# Fubarino_SD_v15.net
KiCad netlist of a schematic drawn in EAGLE
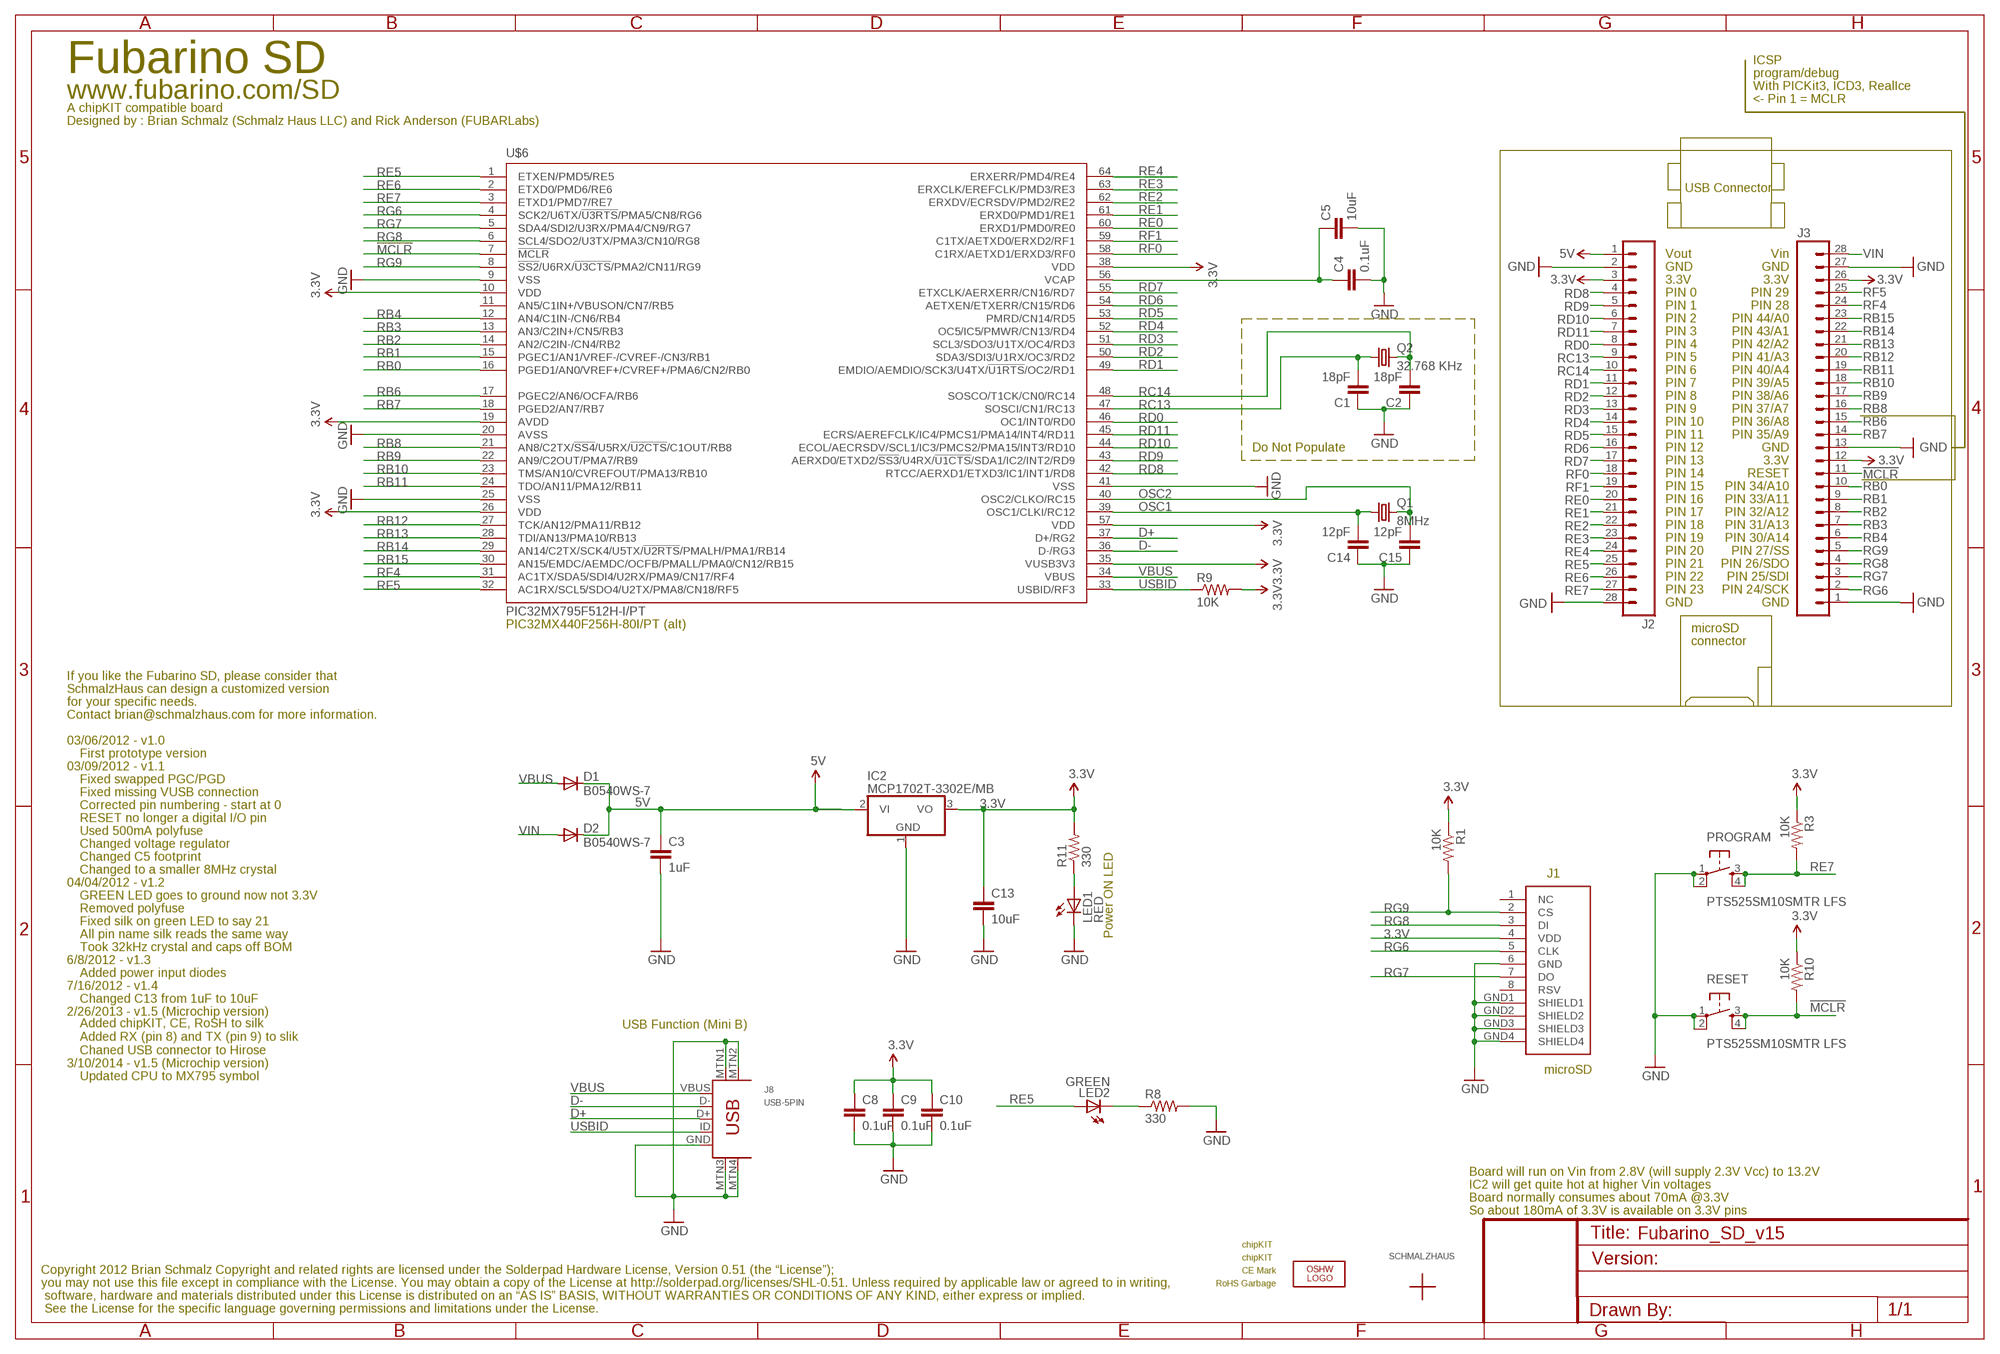
[diagram p0: schematic, sheet 1]

(export (version "E")
  (design (tool "Eeschema 10.0.6"))
  (components
    (comp (ref "C1")
      (value "18pF")
      (footprint "eagle-import:0603-CAP")
      (libsource (lib "eagle-import") (part "SparkFun_CAP0603-CAP"))
    )
    (comp (ref "C2")
      (value "18pF")
      (footprint "eagle-import:0603-CAP")
      (libsource (lib "eagle-import") (part "SparkFun_CAP0603-CAP"))
    )
    (comp (ref "C3")
      (value "1uF")
      (footprint "eagle-import:0603-CAP")
      (libsource (lib "eagle-import") (part "SparkFun_CAP0603-CAP"))
    )
    (comp (ref "C4")
      (value "0.1uF")
      (footprint "eagle-import:0603-CAP")
      (libsource (lib "eagle-import") (part "SparkFun_CAP0603-CAP"))
    )
    (comp (ref "C5")
      (value "10uF")
      (footprint "eagle-import:0805")
      (libsource (lib "eagle-import") (part "CAP0805"))
    )
    (comp (ref "C8")
      (value "0.1uF")
      (footprint "eagle-import:0603-CAP")
      (libsource (lib "eagle-import") (part "SparkFun_CAP0603-CAP"))
    )
    (comp (ref "C9")
      (value "0.1uF")
      (footprint "eagle-import:0603-CAP")
      (libsource (lib "eagle-import") (part "SparkFun_CAP0603-CAP"))
    )
    (comp (ref "C10")
      (value "0.1uF")
      (footprint "eagle-import:0603")
      (libsource (lib "eagle-import") (part "CAP0603"))
    )
    (comp (ref "C13")
      (value "10uF")
      (footprint "eagle-import:0805")
      (libsource (lib "eagle-import") (part "SparkFun02-20-08_CAP0805"))
    )
    (comp (ref "C14")
      (value "12pF")
      (footprint "eagle-import:0603-CAP")
      (libsource (lib "eagle-import") (part "SparkFun_CAP0603-CAP"))
    )
    (comp (ref "C15")
      (value "12pF")
      (footprint "eagle-import:0603-CAP")
      (libsource (lib "eagle-import") (part "SparkFun_CAP0603-CAP"))
    )
    (comp (ref "D1")
      (value "B0540WS-7")
      (footprint "eagle-import:SOD-323")
      (libsource (lib "eagle-import") (part "DIODESOD"))
    )
    (comp (ref "D2")
      (value "B0540WS-7")
      (footprint "eagle-import:SOD-323")
      (libsource (lib "eagle-import") (part "DIODESOD"))
    )
    (comp (ref "IC2")
      (value "MCP1702T-3302E/MB")
      (footprint "eagle-import:SOT89")
      (libsource (lib "eagle-import") (part "MCP1703MB33"))
    )
    (comp (ref "J1")
      (value "MICRO_SD_CARD_SOCKET")
      (footprint "eagle-import:SD-MMC_SOCKET-PP")
      (libsource (lib "eagle-import") (part "MICRO_SD_CARD_SOCKET"))
    )
    (comp (ref "J2")
      (value "M28USEPIN1")
      (footprint "eagle-import:1X28")
      (libsource (lib "eagle-import") (part "M28USEPIN1"))
    )
    (comp (ref "J3")
      (value "M28NOPIN1")
      (footprint "eagle-import:1X28_NO_PIN_1")
      (libsource (lib "eagle-import") (part "M28NOPIN1"))
    )
    (comp (ref "J8")
      (value "USB-5PIN")
      (footprint "eagle-import:USB-MINIB-5PIN-HIROSE-UX60-MB-5ST")
      (libsource (lib "eagle-import") (part "USB-5PIN"))
    )
    (comp (ref "LED1")
      (value "RED")
      (footprint "eagle-import:LED-0603")
      (libsource (lib "eagle-import") (part "LED0603"))
    )
    (comp (ref "LED2")
      (value "GREEN")
      (footprint "eagle-import:LED-0603")
      (libsource (lib "eagle-import") (part "LED0603"))
    )
    (comp (ref "LOGO1")
      (value "OSHW_LOGO_8MILX0070-NT")
      (footprint "eagle-import:OSHW_8X70_NOTEXT")
      (libsource (lib "eagle-import") (part "OSHW_LOGO_8MILX0070-NT"))
    )
    (comp (ref "PROGRAM")
      (value "PTS525SM10SMTR LFS")
      (footprint "eagle-import:TACTILE_SWITCH_SMD")
      (libsource (lib "eagle-import") (part "TAC_SWITCHSND"))
    )
    (comp (ref "Q1")
      (value "8MHz")
      (footprint "eagle-import:NX5032_5MM_3.2MM_CRYSTAL")
      (libsource (lib "eagle-import") (part "CRYSTALNX5032"))
    )
    (comp (ref "Q2")
      (value "32.768 KHz")
      (footprint "eagle-import:TC26H")
      (libsource (lib "eagle-import") (part "CRYSTALTC26H"))
    )
    (comp (ref "R1")
      (value "10K")
      (footprint "eagle-import:0603-RES")
      (libsource (lib "eagle-import") (part "RESISTOR0603-RES"))
    )
    (comp (ref "R3")
      (value "10K")
      (footprint "eagle-import:0603-RES")
      (libsource (lib "eagle-import") (part "RESISTOR0603-RES"))
    )
    (comp (ref "R8")
      (value "330")
      (footprint "eagle-import:0603-RES")
      (libsource (lib "eagle-import") (part "RESISTOR0603-RES"))
    )
    (comp (ref "R9")
      (value "10K")
      (footprint "eagle-import:0603-RES")
      (libsource (lib "eagle-import") (part "RESISTOR0603-RES"))
    )
    (comp (ref "R10")
      (value "10K")
      (footprint "eagle-import:0603-RES")
      (libsource (lib "eagle-import") (part "RESISTOR0603-RES"))
    )
    (comp (ref "R11")
      (value "330")
      (footprint "eagle-import:0603-RES")
      (libsource (lib "eagle-import") (part "RESISTOR0603-RES"))
    )
    (comp (ref "RESET")
      (value "PTS525SM10SMTR LFS")
      (footprint "eagle-import:TACTILE_SWITCH_SMD")
      (libsource (lib "eagle-import") (part "TAC_SWITCHSND"))
    )
    (comp (ref "U$1")
      (value "SCHMALZHAUSSCHMALZHAUS_SMALL")
      (footprint "eagle-import:SCHMALZHAUS_SMALL")
      (libsource (lib "eagle-import") (part "SCHMALZHAUSSCHMALZHAUS_SMALL"))
    )
    (comp (ref "U$2")
      (value "CE_MARK5MM")
      (footprint "eagle-import:CE_5MM")
      (libsource (lib "eagle-import") (part "CE_MARK5MM"))
    )
    (comp (ref "U$3")
      (value "ROHS_GARBAGE")
      (footprint "eagle-import:ROHS_GARBAGE_5MM")
      (libsource (lib "eagle-import") (part "ROHS_GARBAGE"))
    )
    (comp (ref "U$4")
      (value "CHIPKIT2MM")
      (footprint "eagle-import:CHIPKIT_2MM")
      (libsource (lib "eagle-import") (part "CHIPKIT2MM"))
    )
    (comp (ref "U$5")
      (value "CHIPKIT2MM")
      (footprint "eagle-import:CHIPKIT_2MM")
      (libsource (lib "eagle-import") (part "CHIPKIT2MM"))
    )
    (comp (ref "U$6")
      (value "PIC32MX795F512H-I/PT")
      (footprint "eagle-import:TQFP64-10X10")
      (libsource (lib "eagle-import") (part "PIC32MX795F512H-I/PT"))
    )
  )
  (nets
    (net (code "1") (name "/D+") (class "Default")
      (node (ref "J8") (pin "D+") (pinfunction "D+_D+") (pintype "bidirectional"))
      (node (ref "U$6") (pin "37") (pinfunction "D+/RG2_37") (pintype "bidirectional"))
    )
    (net (code "2") (name "/D-") (class "Default")
      (node (ref "J8") (pin "D-") (pinfunction "D-_D-") (pintype "bidirectional"))
      (node (ref "U$6") (pin "36") (pinfunction "D-/RG3_36") (pintype "bidirectional"))
    )
    (net (code "3") (name "/OSC1") (class "Default")
      (node (ref "C14") (pin "2") (pinfunction "2_2") (pintype "passive"))
      (node (ref "Q1") (pin "1") (pinfunction "1_1") (pintype "passive"))
      (node (ref "U$6") (pin "39") (pinfunction "OSC1/CLKI/RC12_39") (pintype "bidirectional"))
    )
    (net (code "4") (name "/OSC2") (class "Default")
      (node (ref "C15") (pin "2") (pinfunction "2_2") (pintype "passive"))
      (node (ref "Q1") (pin "2") (pinfunction "2_2") (pintype "passive"))
      (node (ref "U$6") (pin "40") (pinfunction "OSC2/CLKO/RC15_40") (pintype "bidirectional"))
    )
    (net (code "5") (name "/RB0") (class "Default")
      (node (ref "J3") (pin "10") (pinfunction "10_10") (pintype "passive"))
      (node (ref "U$6") (pin "16") (pinfunction "PGED1/AN0/VREF+/CVREF+/PMA6/CN2/RB0_16") (pintype "bidirectional"))
    )
    (net (code "6") (name "/RB1") (class "Default")
      (node (ref "J3") (pin "9") (pinfunction "9_9") (pintype "passive"))
      (node (ref "U$6") (pin "15") (pinfunction "PGEC1/AN1/VREF-/CVREF-/CN3/RB1_15") (pintype "bidirectional"))
    )
    (net (code "7") (name "/RB2") (class "Default")
      (node (ref "J3") (pin "8") (pinfunction "8_8") (pintype "passive"))
      (node (ref "U$6") (pin "14") (pinfunction "AN2/C2IN-/CN4/RB2_14") (pintype "bidirectional"))
    )
    (net (code "8") (name "/RB3") (class "Default")
      (node (ref "J3") (pin "7") (pinfunction "7_7") (pintype "passive"))
      (node (ref "U$6") (pin "13") (pinfunction "AN3/C2IN+/CN5/RB3_13") (pintype "bidirectional"))
    )
    (net (code "9") (name "/RB4") (class "Default")
      (node (ref "J3") (pin "6") (pinfunction "6_6") (pintype "passive"))
      (node (ref "U$6") (pin "12") (pinfunction "AN4/C1IN-/CN6/RB4_12") (pintype "bidirectional"))
    )
    (net (code "10") (name "/RB6") (class "Default")
      (node (ref "J3") (pin "15") (pinfunction "15_15") (pintype "passive"))
      (node (ref "U$6") (pin "17") (pinfunction "PGEC2/AN6/OCFA/RB6_17") (pintype "bidirectional"))
    )
    (net (code "11") (name "/RB7") (class "Default")
      (node (ref "J3") (pin "14") (pinfunction "14_14") (pintype "passive"))
      (node (ref "U$6") (pin "18") (pinfunction "PGED2/AN7/RB7_18") (pintype "bidirectional"))
    )
    (net (code "12") (name "/RB8") (class "Default")
      (node (ref "J3") (pin "16") (pinfunction "16_16") (pintype "passive"))
      (node (ref "U$6") (pin "21") (pinfunction "AN8/C2TX/~{SS4}/U5RX/~{U2CTS}/C1OUT/RB8_21") (pintype "bidirectional"))
    )
    (net (code "13") (name "/RB9") (class "Default")
      (node (ref "J3") (pin "17") (pinfunction "17_17") (pintype "passive"))
      (node (ref "U$6") (pin "22") (pinfunction "AN9/C2OUT/PMA7/RB9_22") (pintype "bidirectional"))
    )
    (net (code "14") (name "/RB10") (class "Default")
      (node (ref "J3") (pin "18") (pinfunction "18_18") (pintype "passive"))
      (node (ref "U$6") (pin "23") (pinfunction "TMS/AN10/CVREFOUT/PMA13/RB10_23") (pintype "input"))
    )
    (net (code "15") (name "/RB11") (class "Default")
      (node (ref "J3") (pin "19") (pinfunction "19_19") (pintype "passive"))
      (node (ref "U$6") (pin "24") (pinfunction "TDO/AN11/PMA12/RB11_24") (pintype "bidirectional"))
    )
    (net (code "16") (name "/RB12") (class "Default")
      (node (ref "J3") (pin "20") (pinfunction "20_20") (pintype "passive"))
      (node (ref "U$6") (pin "27") (pinfunction "TCK/AN12/PMA11/RB12_27") (pintype "input"))
    )
    (net (code "17") (name "/RB13") (class "Default")
      (node (ref "J3") (pin "21") (pinfunction "21_21") (pintype "passive"))
      (node (ref "U$6") (pin "28") (pinfunction "TDI/AN13/PMA10/RB13_28") (pintype "input"))
    )
    (net (code "18") (name "/RB14") (class "Default")
      (node (ref "J3") (pin "22") (pinfunction "22_22") (pintype "passive"))
      (node (ref "U$6") (pin "29") (pinfunction "AN14/C2TX/SCK4/U5TX/~{U2RTS}/PMALH/PMA1/RB14_29") (pintype "bidirectional"))
    )
    (net (code "19") (name "/RB15") (class "Default")
      (node (ref "J3") (pin "23") (pinfunction "23_23") (pintype "passive"))
      (node (ref "U$6") (pin "30") (pinfunction "AN15/EMDC/AEMDC/OCFB/PMALL/PMA0/CN12/RB15_30") (pintype "bidirectional"))
    )
    (net (code "20") (name "/RC13") (class "Default")
      (node (ref "C1") (pin "2") (pinfunction "2_2") (pintype "passive"))
      (node (ref "J2") (pin "9") (pinfunction "9_9") (pintype "passive"))
      (node (ref "Q2") (pin "1") (pinfunction "1_1") (pintype "passive"))
      (node (ref "U$6") (pin "47") (pinfunction "SOSCI/CN1/RC13_47") (pintype "bidirectional"))
    )
    (net (code "21") (name "/RC14") (class "Default")
      (node (ref "C2") (pin "2") (pinfunction "2_2") (pintype "passive"))
      (node (ref "J2") (pin "10") (pinfunction "10_10") (pintype "passive"))
      (node (ref "Q2") (pin "2") (pinfunction "2_2") (pintype "passive"))
      (node (ref "U$6") (pin "48") (pinfunction "SOSCO/T1CK/CN0/RC14_48") (pintype "bidirectional"))
    )
    (net (code "22") (name "/RD0") (class "Default")
      (node (ref "J2") (pin "8") (pinfunction "8_8") (pintype "passive"))
      (node (ref "U$6") (pin "46") (pinfunction "OC1/INT0/RD0_46") (pintype "bidirectional"))
    )
    (net (code "23") (name "/RD1") (class "Default")
      (node (ref "J2") (pin "11") (pinfunction "11_11") (pintype "passive"))
      (node (ref "U$6") (pin "49") (pinfunction "EMDIO/AEMDIO/SCK3/U4TX/~{U1RTS}/OC2/RD1_49") (pintype "bidirectional"))
    )
    (net (code "24") (name "/RD2") (class "Default")
      (node (ref "J2") (pin "12") (pinfunction "12_12") (pintype "passive"))
      (node (ref "U$6") (pin "50") (pinfunction "SDA3/SDI3/U1RX/OC3/RD2_50") (pintype "bidirectional"))
    )
    (net (code "25") (name "/RD3") (class "Default")
      (node (ref "J2") (pin "13") (pinfunction "13_13") (pintype "passive"))
      (node (ref "U$6") (pin "51") (pinfunction "SCL3/SDO3/U1TX/OC4/RD3_51") (pintype "bidirectional"))
    )
    (net (code "26") (name "/RD4") (class "Default")
      (node (ref "J2") (pin "14") (pinfunction "14_14") (pintype "passive"))
      (node (ref "U$6") (pin "52") (pinfunction "OC5/IC5/PMWR/CN13/RD4_52") (pintype "bidirectional"))
    )
    (net (code "27") (name "/RD5") (class "Default")
      (node (ref "J2") (pin "15") (pinfunction "15_15") (pintype "passive"))
      (node (ref "U$6") (pin "53") (pinfunction "PMRD/CN14/RD5_53") (pintype "bidirectional"))
    )
    (net (code "28") (name "/RD6") (class "Default")
      (node (ref "J2") (pin "16") (pinfunction "16_16") (pintype "passive"))
      (node (ref "U$6") (pin "54") (pinfunction "AETXEN/ETXERR/CN15/RD6_54") (pintype "bidirectional"))
    )
    (net (code "29") (name "/RD7") (class "Default")
      (node (ref "J2") (pin "17") (pinfunction "17_17") (pintype "passive"))
      (node (ref "U$6") (pin "55") (pinfunction "ETXCLK/AERXERR/CN16/RD7_55") (pintype "bidirectional"))
    )
    (net (code "30") (name "/RD8") (class "Default")
      (node (ref "J2") (pin "4") (pinfunction "4_4") (pintype "passive"))
      (node (ref "U$6") (pin "42") (pinfunction "RTCC/AERXD1/ETXD3/IC1/INT1/RD8_42") (pintype "bidirectional"))
    )
    (net (code "31") (name "/RD9") (class "Default")
      (node (ref "J2") (pin "5") (pinfunction "5_5") (pintype "passive"))
      (node (ref "U$6") (pin "43") (pinfunction "AERXD0/ETXD2/~{SS3}/U4RX/~{U1CTS}/SDA1/IC2/INT2/RD9_43") (pintype "bidirectional"))
    )
    (net (code "32") (name "/RD10") (class "Default")
      (node (ref "J2") (pin "6") (pinfunction "6_6") (pintype "passive"))
      (node (ref "U$6") (pin "44") (pinfunction "ECOL/AECRSDV/SCL1/IC3/PMCS2/PMA15/INT3/RD10_44") (pintype "bidirectional"))
    )
    (net (code "33") (name "/RD11") (class "Default")
      (node (ref "J2") (pin "7") (pinfunction "7_7") (pintype "passive"))
      (node (ref "U$6") (pin "45") (pinfunction "ECRS/AEREFCLK/IC4/PMCS1/PMA14/INT4/RD11_45") (pintype "bidirectional"))
    )
    (net (code "34") (name "/RE0") (class "Default")
      (node (ref "J2") (pin "20") (pinfunction "20_20") (pintype "passive"))
      (node (ref "U$6") (pin "60") (pinfunction "ERXD1/PMD0/RE0_60") (pintype "bidirectional"))
    )
    (net (code "35") (name "/RE1") (class "Default")
      (node (ref "J2") (pin "21") (pinfunction "21_21") (pintype "passive"))
      (node (ref "U$6") (pin "61") (pinfunction "ERXD0/PMD1/RE1_61") (pintype "bidirectional"))
    )
    (net (code "36") (name "/RE2") (class "Default")
      (node (ref "J2") (pin "22") (pinfunction "22_22") (pintype "passive"))
      (node (ref "U$6") (pin "62") (pinfunction "ERXDV/ECRSDV/PMD2/RE2_62") (pintype "bidirectional"))
    )
    (net (code "37") (name "/RE3") (class "Default")
      (node (ref "J2") (pin "23") (pinfunction "23_23") (pintype "passive"))
      (node (ref "U$6") (pin "63") (pinfunction "ERXCLK/EREFCLK/PMD3/RE3_63") (pintype "bidirectional"))
    )
    (net (code "38") (name "/RE4") (class "Default")
      (node (ref "J2") (pin "24") (pinfunction "24_24") (pintype "passive"))
      (node (ref "U$6") (pin "64") (pinfunction "ERXERR/PMD4/RE4_64") (pintype "bidirectional"))
    )
    (net (code "39") (name "/RE5") (class "Default")
      (node (ref "J2") (pin "25") (pinfunction "25_25") (pintype "passive"))
      (node (ref "LED2") (pin "A") (pinfunction "A_A") (pintype "passive"))
      (node (ref "U$6") (pin "1") (pinfunction "ETXEN/PMD5/RE5_1") (pintype "bidirectional"))
    )
    (net (code "40") (name "/RE6") (class "Default")
      (node (ref "J2") (pin "26") (pinfunction "26_26") (pintype "passive"))
      (node (ref "U$6") (pin "2") (pinfunction "ETXD0/PMD6/RE6_2") (pintype "bidirectional"))
    )
    (net (code "41") (name "/RE7") (class "Default")
      (node (ref "J2") (pin "27") (pinfunction "27_27") (pintype "passive"))
      (node (ref "PROGRAM") (pin "3") (pinfunction "3_3") (pintype "passive"))
      (node (ref "PROGRAM") (pin "4") (pinfunction "4_4") (pintype "passive"))
      (node (ref "R3") (pin "2") (pinfunction "2_2") (pintype "passive"))
      (node (ref "U$6") (pin "3") (pinfunction "ETXD1/PMD7/RE7_3") (pintype "bidirectional"))
    )
    (net (code "42") (name "/RF0") (class "Default")
      (node (ref "J2") (pin "18") (pinfunction "18_18") (pintype "passive"))
      (node (ref "U$6") (pin "58") (pinfunction "C1RX/AETXD1/ERXD3/RF0_58") (pintype "bidirectional"))
    )
    (net (code "43") (name "/RF1") (class "Default")
      (node (ref "J2") (pin "19") (pinfunction "19_19") (pintype "passive"))
      (node (ref "U$6") (pin "59") (pinfunction "C1TX/AETXD0/ERXD2/RF1_59") (pintype "bidirectional"))
    )
    (net (code "44") (name "/RF4") (class "Default")
      (node (ref "J3") (pin "24") (pinfunction "24_24") (pintype "passive"))
      (node (ref "U$6") (pin "31") (pinfunction "AC1TX/SDA5/SDI4/U2RX/PMA9/CN17/RF4_31") (pintype "bidirectional"))
    )
    (net (code "45") (name "/RF5") (class "Default")
      (node (ref "J3") (pin "25") (pinfunction "25_25") (pintype "passive"))
      (node (ref "U$6") (pin "32") (pinfunction "AC1RX/SCL5/SDO4/U2TX/PMA8/CN18/RF5_32") (pintype "bidirectional"))
    )
    (net (code "46") (name "/RG6") (class "Default")
      (node (ref "J1") (pin "5") (pinfunction "CLK_5") (pintype "bidirectional"))
      (node (ref "J3") (pin "2") (pinfunction "2_2") (pintype "passive"))
      (node (ref "U$6") (pin "4") (pinfunction "SCK2/U6TX/~{U3RTS}/PMA5/CN8/RG6_4") (pintype "bidirectional"))
    )
    (net (code "47") (name "/RG7") (class "Default")
      (node (ref "J1") (pin "7") (pinfunction "DO_7") (pintype "bidirectional"))
      (node (ref "J3") (pin "3") (pinfunction "3_3") (pintype "passive"))
      (node (ref "U$6") (pin "5") (pinfunction "SDA4/SDI2/U3RX/PMA4/CN9/RG7_5") (pintype "bidirectional"))
    )
    (net (code "48") (name "/RG8") (class "Default")
      (node (ref "J1") (pin "3") (pinfunction "DI_3") (pintype "bidirectional"))
      (node (ref "J3") (pin "4") (pinfunction "4_4") (pintype "passive"))
      (node (ref "U$6") (pin "6") (pinfunction "SCL4/SDO2/U3TX/PMA3/CN10/RG8_6") (pintype "bidirectional"))
    )
    (net (code "49") (name "/RG9") (class "Default")
      (node (ref "J1") (pin "2") (pinfunction "CS_2") (pintype "bidirectional"))
      (node (ref "J3") (pin "5") (pinfunction "5_5") (pintype "passive"))
      (node (ref "R1") (pin "2") (pinfunction "2_2") (pintype "passive"))
      (node (ref "U$6") (pin "8") (pinfunction "~{SS2}/U6RX/~{U3CTS}/PMA2/CN11/RG9_8") (pintype "bidirectional"))
    )
    (net (code "50") (name "/USBID") (class "Default")
      (node (ref "J8") (pin "ID") (pinfunction "ID_ID") (pintype "bidirectional"))
      (node (ref "R9") (pin "1") (pinfunction "1_1") (pintype "passive"))
      (node (ref "U$6") (pin "33") (pinfunction "USBID/RF3_33") (pintype "bidirectional"))
    )
    (net (code "51") (name "/VBUS") (class "Default")
      (node (ref "D1") (pin "2") (pinfunction "A_2") (pintype "passive"))
      (node (ref "J8") (pin "VBUS") (pinfunction "VBUS_VBUS") (pintype "bidirectional"))
      (node (ref "U$6") (pin "34") (pinfunction "VBUS_34") (pintype "bidirectional"))
    )
    (net (code "52") (name "/VIN") (class "Default")
      (node (ref "D2") (pin "2") (pinfunction "A_2") (pintype "passive"))
      (node (ref "J3") (pin "28") (pinfunction "28_28") (pintype "passive"))
    )
    (net (code "53") (name "/~{MCLR}") (class "Default")
      (node (ref "J3") (pin "11") (pinfunction "11_11") (pintype "passive"))
      (node (ref "R10") (pin "2") (pinfunction "2_2") (pintype "passive"))
      (node (ref "RESET") (pin "3") (pinfunction "3_3") (pintype "passive"))
      (node (ref "RESET") (pin "4") (pinfunction "4_4") (pintype "passive"))
      (node (ref "U$6") (pin "7") (pinfunction "~{MCLR}_7") (pintype "input"))
    )
    (net (code "54") (name "3.3V") (class "Default")
      (node (ref "C10") (pin "1") (pinfunction "1_1") (pintype "passive"))
      (node (ref "C13") (pin "1") (pinfunction "1_1") (pintype "passive"))
      (node (ref "C8") (pin "1") (pinfunction "1_1") (pintype "passive"))
      (node (ref "C9") (pin "1") (pinfunction "1_1") (pintype "passive"))
      (node (ref "IC2") (pin "3") (pinfunction "VO_3") (pintype "passive"))
      (node (ref "J1") (pin "4") (pinfunction "VDD_4") (pintype "bidirectional"))
      (node (ref "J2") (pin "3") (pinfunction "3_3") (pintype "passive"))
      (node (ref "J3") (pin "12") (pinfunction "12_12") (pintype "passive"))
      (node (ref "J3") (pin "26") (pinfunction "26_26") (pintype "passive"))
      (node (ref "R1") (pin "1") (pinfunction "1_1") (pintype "passive"))
      (node (ref "R10") (pin "1") (pinfunction "1_1") (pintype "passive"))
      (node (ref "R11") (pin "2") (pinfunction "2_2") (pintype "passive"))
      (node (ref "R3") (pin "1") (pinfunction "1_1") (pintype "passive"))
      (node (ref "R9") (pin "2") (pinfunction "2_2") (pintype "passive"))
      (node (ref "U$6") (pin "10") (pinfunction "VDD_10") (pintype "power_in"))
      (node (ref "U$6") (pin "19") (pinfunction "AVDD_19") (pintype "power_in"))
      (node (ref "U$6") (pin "26") (pinfunction "VDD_26") (pintype "power_in"))
      (node (ref "U$6") (pin "35") (pinfunction "VUSB3V3_35") (pintype "passive"))
      (node (ref "U$6") (pin "38") (pinfunction "VDD_38") (pintype "passive"))
      (node (ref "U$6") (pin "57") (pinfunction "VDD_57") (pintype "power_in"))
    )
    (net (code "55") (name "5V") (class "Default")
      (node (ref "C3") (pin "1") (pinfunction "1_1") (pintype "passive"))
      (node (ref "D1") (pin "1") (pinfunction "C_1") (pintype "passive"))
      (node (ref "D2") (pin "1") (pinfunction "C_1") (pintype "passive"))
      (node (ref "IC2") (pin "2") (pinfunction "VI_2") (pintype "input"))
      (node (ref "IC2") (pin "2@1") (pinfunction "VI1_2@1") (pintype "input"))
      (node (ref "J2") (pin "1") (pinfunction "1_1") (pintype "passive"))
    )
    (net (code "56") (name "GND") (class "Default")
      (node (ref "C1") (pin "1") (pinfunction "1_1") (pintype "passive"))
      (node (ref "C10") (pin "2") (pinfunction "2_2") (pintype "passive"))
      (node (ref "C13") (pin "2") (pinfunction "2_2") (pintype "passive"))
      (node (ref "C14") (pin "1") (pinfunction "1_1") (pintype "passive"))
      (node (ref "C15") (pin "1") (pinfunction "1_1") (pintype "passive"))
      (node (ref "C2") (pin "1") (pinfunction "1_1") (pintype "passive"))
      (node (ref "C3") (pin "2") (pinfunction "2_2") (pintype "passive"))
      (node (ref "C4") (pin "2") (pinfunction "2_2") (pintype "passive"))
      (node (ref "C5") (pin "2") (pinfunction "2_2") (pintype "passive"))
      (node (ref "C8") (pin "2") (pinfunction "2_2") (pintype "passive"))
      (node (ref "C9") (pin "2") (pinfunction "2_2") (pintype "passive"))
      (node (ref "IC2") (pin "1") (pinfunction "GND_1") (pintype "passive"))
      (node (ref "J1") (pin "6") (pinfunction "GND_6") (pintype "bidirectional"))
      (node (ref "J1") (pin "GND1") (pinfunction "SHIELD1_GND1") (pintype "bidirectional"))
      (node (ref "J1") (pin "GND2") (pinfunction "SHIELD2_GND2") (pintype "bidirectional"))
      (node (ref "J1") (pin "GND3") (pinfunction "SHIELD3_GND3") (pintype "bidirectional"))
      (node (ref "J1") (pin "GND4") (pinfunction "SHIELD4_GND4") (pintype "bidirectional"))
      (node (ref "J2") (pin "2") (pinfunction "2_2") (pintype "passive"))
      (node (ref "J2") (pin "28") (pinfunction "28_28") (pintype "passive"))
      (node (ref "J3") (pin "1") (pinfunction "1_1") (pintype "passive"))
      (node (ref "J3") (pin "13") (pinfunction "13_13") (pintype "passive"))
      (node (ref "J3") (pin "27") (pinfunction "27_27") (pintype "passive"))
      (node (ref "J8") (pin "GND") (pinfunction "GND_GND") (pintype "bidirectional"))
      (node (ref "J8") (pin "MTN1") (pinfunction "MTN1_MTN1") (pintype "bidirectional"))
      (node (ref "J8") (pin "MTN2") (pinfunction "MTN2_MTN2") (pintype "bidirectional"))
      (node (ref "J8") (pin "MTN3") (pinfunction "MTN3_MTN3") (pintype "bidirectional"))
      (node (ref "J8") (pin "MTN4") (pinfunction "MTN4_MTN4") (pintype "bidirectional"))
      (node (ref "LED1") (pin "C") (pinfunction "C_C") (pintype "passive"))
      (node (ref "PROGRAM") (pin "1") (pinfunction "1_1") (pintype "passive"))
      (node (ref "PROGRAM") (pin "2") (pinfunction "2_2") (pintype "passive"))
      (node (ref "R8") (pin "2") (pinfunction "2_2") (pintype "passive"))
      (node (ref "RESET") (pin "1") (pinfunction "1_1") (pintype "passive"))
      (node (ref "RESET") (pin "2") (pinfunction "2_2") (pintype "passive"))
      (node (ref "U$6") (pin "20") (pinfunction "AVSS_20") (pintype "power_in"))
      (node (ref "U$6") (pin "25") (pinfunction "VSS_25") (pintype "power_in"))
      (node (ref "U$6") (pin "41") (pinfunction "VSS_41") (pintype "power_in"))
      (node (ref "U$6") (pin "9") (pinfunction "VSS_9") (pintype "power_in"))
    )
    (net (code "57") (name "Net-(LED1-PadA)") (class "Default")
      (node (ref "LED1") (pin "A") (pinfunction "A_A") (pintype "passive"))
      (node (ref "R11") (pin "1") (pinfunction "1_1") (pintype "passive"))
    )
    (net (code "58") (name "Net-(LED2-PadC)") (class "Default")
      (node (ref "LED2") (pin "C") (pinfunction "C_C") (pintype "passive"))
      (node (ref "R8") (pin "1") (pinfunction "1_1") (pintype "passive"))
    )
    (net (code "59") (name "Net-(U$6-VCAP)") (class "Default")
      (node (ref "C4") (pin "1") (pinfunction "1_1") (pintype "passive"))
      (node (ref "C5") (pin "1") (pinfunction "1_1") (pintype "passive"))
      (node (ref "U$6") (pin "56") (pinfunction "VCAP_56") (pintype "power_in"))
    )
    (net (code "60") (name "unconnected-(J1-NC-Pad1)") (class "Default")
      (node (ref "J1") (pin "1") (pinfunction "NC_1") (pintype "bidirectional"))
    )
    (net (code "61") (name "unconnected-(J1-RSV-Pad8)") (class "Default")
      (node (ref "J1") (pin "8") (pinfunction "RSV_8") (pintype "bidirectional"))
    )
    (net (code "62") (name "unconnected-(U$6-AN5{slash}C1IN+{slash}VBUSON{slash}CN7{slash}RB5-Pad11)") (class "Default")
      (node (ref "U$6") (pin "11") (pinfunction "AN5/C1IN+/VBUSON/CN7/RB5_11") (pintype "bidirectional"))
    )
  )
)
